# OSP_Carrier_V7_Release_USB.net
KiCad netlist of a schematic drawn in Altium Designer
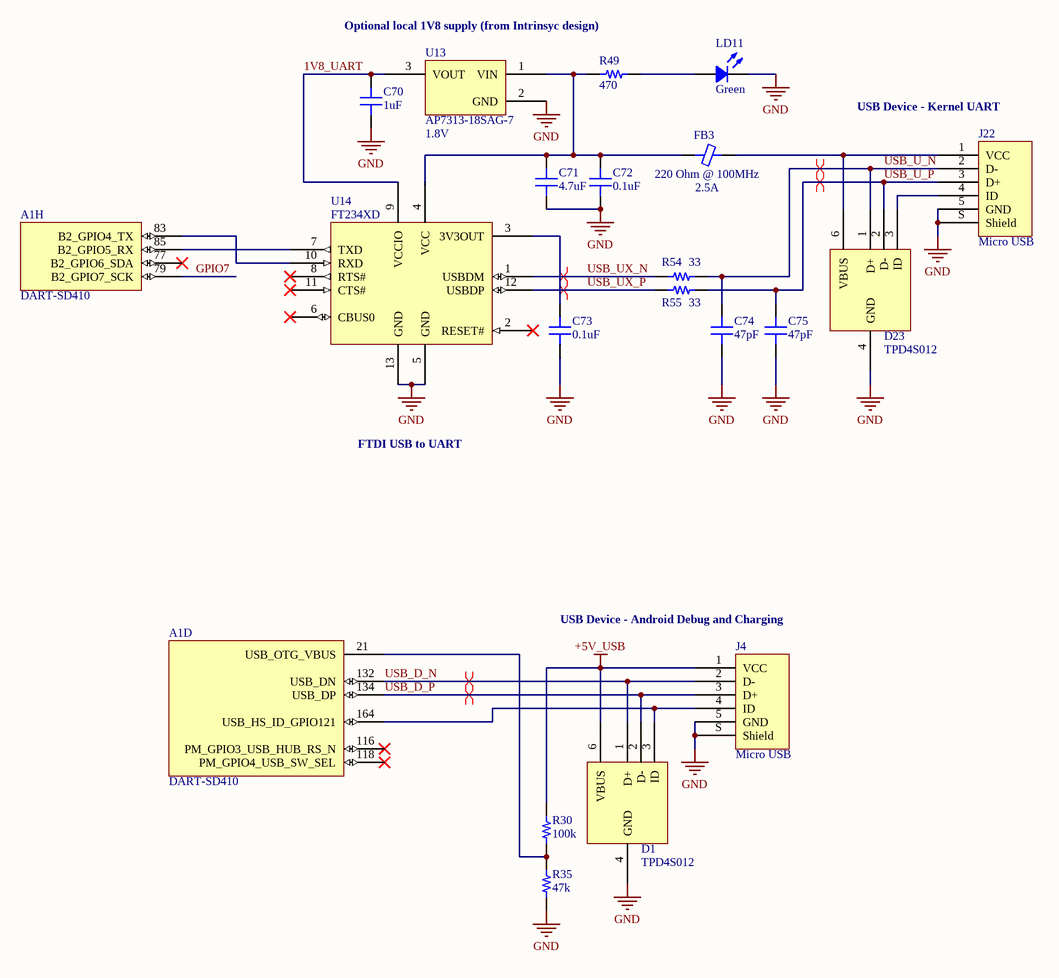
[diagram p0: OSP_Carrier_V7_Release_USB.SchDoc]

(export (version "E")
  (design (tool "Eeschema 10.0.6"))
  (components
    (comp (ref "A1")
      (value "DART-SD410")
      (footprint "DART-SD410")
      (description "Variscite DART-SD410 System on Module")
      (libsource (lib "DART-SD410") (part "DART-SD410"))
    )
    (comp (ref "C70")
      (value "1uF")
      (footprint "CAP 0603/1608")
      (description "CAP CER 1UF 25V X7R 0603")
      (fields
        (field (name "PART NUMBER") "C1608X7R1E105K080AB")
        (field (name "MANUFACTURER") "TDK Corporation")
      )
      (libsource (lib "Celestial Library Database") (part "Capacitor"))
    )
    (comp (ref "C71")
      (value "4.7uF")
      (footprint "CAP 0402/1005")
      (description "CAP CER 4.7UF 10V X5R 0402")
      (fields
        (field (name "PART NUMBER") "C1005X5R1A475K050BC")
        (field (name "MANUFACTURER") "TDK Corporation")
      )
      (libsource (lib "Celestial Library Database") (part "Capacitor"))
    )
    (comp (ref "C72")
      (value "0.1uF")
      (footprint "CAP 0402/1005")
      (description "CAP CER 0.1UF 50V X7R 0402")
      (fields
        (field (name "PART NUMBER") "C1005X7R1H104K050BB")
        (field (name "MANUFACTURER") "TDK Corporation")
      )
      (libsource (lib "Celestial Library Database") (part "Capacitor"))
    )
    (comp (ref "C73")
      (value "0.1uF")
      (footprint "CAP 0402/1005")
      (description "CAP CER 0.1UF 50V X7R 0402")
      (fields
        (field (name "PART NUMBER") "C1005X7R1H104K050BB")
        (field (name "MANUFACTURER") "TDK Corporation")
      )
      (libsource (lib "Celestial Library Database") (part "Capacitor"))
    )
    (comp (ref "C74")
      (value "47pF")
      (footprint "CAP 0402/1005")
      (description "CAP CER 47PF 50V C0G 0402")
      (fields
        (field (name "PART NUMBER") "C1005C0G1H470G050BA")
        (field (name "MANUFACTURER") "TDK Corporation")
      )
      (libsource (lib "Celestial Library Database") (part "Capacitor"))
    )
    (comp (ref "C75")
      (value "47pF")
      (footprint "CAP 0402/1005")
      (description "CAP CER 47PF 50V C0G 0402")
      (fields
        (field (name "PART NUMBER") "C1005C0G1H470G050BA")
        (field (name "MANUFACTURER") "TDK Corporation")
      )
      (libsource (lib "Celestial Library Database") (part "Capacitor"))
    )
    (comp (ref "D1")
      (value "TPD4S012")
      (footprint "TI_SON6")
      (description "TI TPD4S012 USB ESD Protection")
      (libsource (lib "OSP_Symbols") (part "TI_TPD4S012"))
    )
    (comp (ref "D23")
      (value "TPD4S012")
      (footprint "TI_SON6")
      (description "TI TPD4S012 USB ESD Protection")
      (libsource (lib "OSP_Symbols") (part "TI_TPD4S012"))
    )
    (comp (ref "FB3")
      (value "220 Ohm @ 100MHz")
      (footprint "FER 0603/1608")
      (description "FERRITE CHIP 220 OHM 2500MA 0603")
      (fields
        (field (name "PART NUMBER") "CIS10P221NC")
        (field (name "MANUFACTURER") "Samsung Electro-Mechanics America, Inc.")
        (field (name "CURRENT RATING") "2.5A")
      )
      (libsource (lib "Celestial Library Database") (part "Ferrite Chip"))
    )
    (comp (ref "J4")
      (value "Micro USB")
      (footprint "FCI USB 10118193-0001LF")
      (description "CONN USB MICRO B RECPT SMT R/A")
      (fields (field (name "PART NUMBER") "10118193-0001LF"))
      (libsource (lib "Celestial Library Database") (part "USB 2.0 Type B Micro"))
    )
    (comp (ref "J22")
      (value "Micro USB")
      (footprint "FCI USB 10118193-0001LF")
      (description "CONN USB MICRO B RECPT SMT R/A")
      (fields (field (name "PART NUMBER") "10118193-0001LF"))
      (libsource (lib "Celestial Library Database") (part "USB 2.0 Type B Micro"))
    )
    (comp (ref "LD11")
      (value "Green")
      (footprint "LED 0603/1608 GREEN")
      (description "LED GREEN CLEAR 0603 SMD")
      (fields (field (name "PART NUMBER") "LTST-C191KGKT") (field (name "MANUFACTURER") "Lite-On Inc."))
      (libsource (lib "Celestial Library Database") (part "LED"))
    )
    (comp (ref "R30")
      (value "100k")
      (footprint "RES 0402/1005")
      (description "RES SMD 100K OHM 1% 1/10W 0402")
      (fields
        (field (name "PART NUMBER") "ERJ-2RKF1003X")
        (field (name "MANUFACTURER") "Panasonic Electronic Components")
      )
      (libsource (lib "Celestial Library Database") (part "Resistor"))
    )
    (comp (ref "R35")
      (value "47k")
      (footprint "RES 0402/1005")
      (description "RES SMD 47K OHM 1% 1/10W 0402")
      (fields
        (field (name "PART NUMBER") "ERJ-2RKF4702X")
        (field (name "MANUFACTURER") "Panasonic Electronic Components")
      )
      (libsource (lib "Celestial Library Database") (part "Resistor"))
    )
    (comp (ref "R49")
      (value "470")
      (footprint "RES 0402/1005")
      (description "RES SMD 470 OHM 1% 1/10W 0402")
      (fields
        (field (name "PART NUMBER") "ERJ-2RKF4700X")
        (field (name "MANUFACTURER") "Panasonic Electronic Components")
      )
      (libsource (lib "Celestial Library Database") (part "Resistor"))
    )
    (comp (ref "R54")
      (value "33")
      (footprint "RES 0402/1005")
      (description "RES SMD 33 OHM 1% 1/10W 0402")
      (fields
        (field (name "PART NUMBER") "ERJ-2RKF33R0X")
        (field (name "MANUFACTURER") "Panasonic Electronic Components")
      )
      (libsource (lib "Celestial Library Database") (part "Resistor"))
    )
    (comp (ref "R55")
      (value "33")
      (footprint "RES 0402/1005")
      (description "RES SMD 33 OHM 1% 1/10W 0402")
      (fields
        (field (name "PART NUMBER") "ERJ-2RKF33R0X")
        (field (name "MANUFACTURER") "Panasonic Electronic Components")
      )
      (libsource (lib "Celestial Library Database") (part "Resistor"))
    )
    (comp (ref "U13")
      (value "AP7313-18SAG-7")
      (footprint "DIODES SOT-23-3")
      (description "IC REG LDO 1.8V 0.15A SOT23-3")
      (fields (field (name "MANUFACTURER") "Diodes Incorporated") (field (name "VOLTAGE - OUTPUT") "1.8V"))
      (libsource (lib "Celestial Library Database") (part "Diodes Inc AP7313"))
    )
    (comp (ref "U14")
      (value "FT234XD")
      (footprint "FTDI_DFN12")
      (description "FTDI FT234XD USB to UART")
      (libsource (lib "OSP_Symbols") (part "FTDI_FT234XD"))
    )
  )
  (nets
    (net (code "1") (name "+5V_USB") (class "Default")
      (node (ref "D1") (pin "6") (pinfunction "VBUS_6") (pintype "passive"))
      (node (ref "J4") (pin "1") (pinfunction "VCC_1") (pintype "passive"))
      (node (ref "R30") (pin "2") (pinfunction "2_2") (pintype "passive"))
    )
    (net (code "2") (name "/1V8_UART") (class "Default")
      (node (ref "C70") (pin "2") (pinfunction "2_2") (pintype "passive"))
      (node (ref "U13") (pin "3") (pinfunction "VOUT_3") (pintype "passive"))
      (node (ref "U14") (pin "9") (pinfunction "VCCIO_9") (pintype "power_in"))
    )
    (net (code "3") (name "/GPIO7") (class "Default")
      (node (ref "A1") (pin "79") (pinfunction "B2_GPIO7_SCK_79") (pintype "bidirectional"))
    )
    (net (code "4") (name "/USB_D_N") (class "Default")
      (node (ref "A1") (pin "132") (pinfunction "USB_DN_132") (pintype "bidirectional"))
      (node (ref "D1") (pin "1") (pinfunction "D+_1") (pintype "passive"))
      (node (ref "J4") (pin "2") (pinfunction "D-_2") (pintype "passive"))
    )
    (net (code "5") (name "/USB_D_P") (class "Default")
      (node (ref "A1") (pin "134") (pinfunction "USB_DP_134") (pintype "bidirectional"))
      (node (ref "D1") (pin "2") (pinfunction "D-_2") (pintype "passive"))
      (node (ref "J4") (pin "3") (pinfunction "D+_3") (pintype "passive"))
    )
    (net (code "6") (name "/USB_UX_N") (class "Default")
      (node (ref "R54") (pin "1") (pinfunction "1_1") (pintype "passive"))
      (node (ref "U14") (pin "1") (pinfunction "USBDM_1") (pintype "bidirectional"))
    )
    (net (code "7") (name "/USB_UX_P") (class "Default")
      (node (ref "R55") (pin "1") (pinfunction "1_1") (pintype "passive"))
      (node (ref "U14") (pin "12") (pinfunction "USBDP_12") (pintype "bidirectional"))
    )
    (net (code "8") (name "/USB_U_N") (class "Default")
      (node (ref "C74") (pin "2") (pinfunction "2_2") (pintype "passive"))
      (node (ref "D23") (pin "1") (pinfunction "D+_1") (pintype "passive"))
      (node (ref "J22") (pin "2") (pinfunction "D-_2") (pintype "passive"))
      (node (ref "R54") (pin "2") (pinfunction "2_2") (pintype "passive"))
    )
    (net (code "9") (name "/USB_U_P") (class "Default")
      (node (ref "C75") (pin "2") (pinfunction "2_2") (pintype "passive"))
      (node (ref "D23") (pin "2") (pinfunction "D-_2") (pintype "passive"))
      (node (ref "J22") (pin "3") (pinfunction "D+_3") (pintype "passive"))
      (node (ref "R55") (pin "2") (pinfunction "2_2") (pintype "passive"))
    )
    (net (code "10") (name "GND") (class "Default")
      (node (ref "C70") (pin "1") (pinfunction "1_1") (pintype "passive"))
      (node (ref "C71") (pin "1") (pinfunction "1_1") (pintype "passive"))
      (node (ref "C72") (pin "1") (pinfunction "1_1") (pintype "passive"))
      (node (ref "C73") (pin "1") (pinfunction "1_1") (pintype "passive"))
      (node (ref "C74") (pin "1") (pinfunction "1_1") (pintype "passive"))
      (node (ref "C75") (pin "1") (pinfunction "1_1") (pintype "passive"))
      (node (ref "D1") (pin "4") (pinfunction "GND_4") (pintype "passive"))
      (node (ref "D23") (pin "4") (pinfunction "GND_4") (pintype "passive"))
      (node (ref "J22") (pin "5") (pinfunction "GND_5") (pintype "passive"))
      (node (ref "J22") (pin "S") (pinfunction "Shield_S") (pintype "passive"))
      (node (ref "J4") (pin "5") (pinfunction "GND_5") (pintype "passive"))
      (node (ref "J4") (pin "S") (pinfunction "Shield_S") (pintype "passive"))
      (node (ref "LD11") (pin "2") (pinfunction "2_2") (pintype "passive"))
      (node (ref "R35") (pin "1") (pinfunction "1_1") (pintype "passive"))
      (node (ref "U13") (pin "2") (pinfunction "GND_2") (pintype "passive"))
      (node (ref "U14") (pin "13") (pinfunction "GND_13") (pintype "power_in"))
      (node (ref "U14") (pin "5") (pinfunction "GND_5") (pintype "power_in"))
    )
    (net (code "11") (name "Net-(A1D-USB_HS_ID_GPIO121)") (class "Default")
      (node (ref "A1") (pin "164") (pinfunction "USB_HS_ID_GPIO121_164") (pintype "bidirectional"))
      (node (ref "D1") (pin "3") (pinfunction "ID_3") (pintype "passive"))
      (node (ref "J4") (pin "4") (pinfunction "ID_4") (pintype "passive"))
    )
    (net (code "12") (name "Net-(A1D-USB_OTG_VBUS)") (class "Default")
      (node (ref "A1") (pin "21") (pinfunction "USB_OTG_VBUS_21") (pintype "power_in"))
      (node (ref "R30") (pin "1") (pinfunction "1_1") (pintype "passive"))
      (node (ref "R35") (pin "2") (pinfunction "2_2") (pintype "passive"))
    )
    (net (code "13") (name "Net-(A1H-B2_GPIO4_TX)") (class "Default")
      (node (ref "A1") (pin "83") (pinfunction "B2_GPIO4_TX_83") (pintype "bidirectional"))
      (node (ref "U14") (pin "10") (pinfunction "RXD_10") (pintype "input"))
    )
    (net (code "14") (name "Net-(A1H-B2_GPIO5_RX)") (class "Default")
      (node (ref "A1") (pin "85") (pinfunction "B2_GPIO5_RX_85") (pintype "bidirectional"))
      (node (ref "U14") (pin "7") (pinfunction "TXD_7") (pintype "output"))
    )
    (net (code "15") (name "Net-(D23-ID)") (class "Default")
      (node (ref "D23") (pin "3") (pinfunction "ID_3") (pintype "passive"))
      (node (ref "J22") (pin "4") (pinfunction "ID_4") (pintype "passive"))
    )
    (net (code "16") (name "Net-(D23-VBUS)") (class "Default")
      (node (ref "D23") (pin "6") (pinfunction "VBUS_6") (pintype "passive"))
      (node (ref "FB3") (pin "2") (pinfunction "2_2") (pintype "passive"))
      (node (ref "J22") (pin "1") (pinfunction "VCC_1") (pintype "passive"))
    )
    (net (code "17") (name "Net-(LD11-Pad1)") (class "Default")
      (node (ref "LD11") (pin "1") (pinfunction "1_1") (pintype "passive"))
      (node (ref "R49") (pin "2") (pinfunction "2_2") (pintype "passive"))
    )
    (net (code "18") (name "Net-(U13-VIN)") (class "Default")
      (node (ref "C71") (pin "2") (pinfunction "2_2") (pintype "passive"))
      (node (ref "C72") (pin "2") (pinfunction "2_2") (pintype "passive"))
      (node (ref "FB3") (pin "1") (pinfunction "1_1") (pintype "passive"))
      (node (ref "R49") (pin "1") (pinfunction "1_1") (pintype "passive"))
      (node (ref "U13") (pin "1") (pinfunction "VIN_1") (pintype "passive"))
      (node (ref "U14") (pin "4") (pinfunction "VCC_4") (pintype "power_in"))
    )
    (net (code "19") (name "Net-(U14-3V3OUT)") (class "Default")
      (node (ref "C73") (pin "2") (pinfunction "2_2") (pintype "passive"))
      (node (ref "U14") (pin "3") (pinfunction "3V3OUT_3") (pintype "power_in"))
    )
    (net (code "20") (name "unconnected-(A1D-PM_GPIO3_USB_HUB_RS_N-Pad116)") (class "Default")
      (node (ref "A1") (pin "116") (pinfunction "PM_GPIO3_USB_HUB_RS_N_116") (pintype "bidirectional+no_connect"))
    )
    (net (code "21") (name "unconnected-(A1D-PM_GPIO4_USB_SW_SEL-Pad118)") (class "Default")
      (node (ref "A1") (pin "118") (pinfunction "PM_GPIO4_USB_SW_SEL_118") (pintype "bidirectional+no_connect"))
    )
    (net (code "22") (name "unconnected-(A1H-B2_GPIO6_SDA-Pad77)") (class "Default")
      (node (ref "A1") (pin "77") (pinfunction "B2_GPIO6_SDA_77") (pintype "bidirectional+no_connect"))
    )
    (net (code "23") (name "unconnected-(U14-CBUS0-Pad6)") (class "Default")
      (node (ref "U14") (pin "6") (pinfunction "CBUS0_6") (pintype "bidirectional+no_connect"))
    )
    (net (code "24") (name "unconnected-(U14-CTS#-Pad11)") (class "Default")
      (node (ref "U14") (pin "11") (pinfunction "CTS#_11") (pintype "input+no_connect"))
    )
    (net (code "25") (name "unconnected-(U14-RESET#-Pad2)") (class "Default")
      (node (ref "U14") (pin "2") (pinfunction "RESET#_2") (pintype "input+no_connect"))
    )
    (net (code "26") (name "unconnected-(U14-RTS#-Pad8)") (class "Default")
      (node (ref "U14") (pin "8") (pinfunction "RTS#_8") (pintype "output+no_connect"))
    )
  )
)
